# INA381A_Overcurrent_Protection.net
KiCad netlist of a schematic drawn in Altium Designer
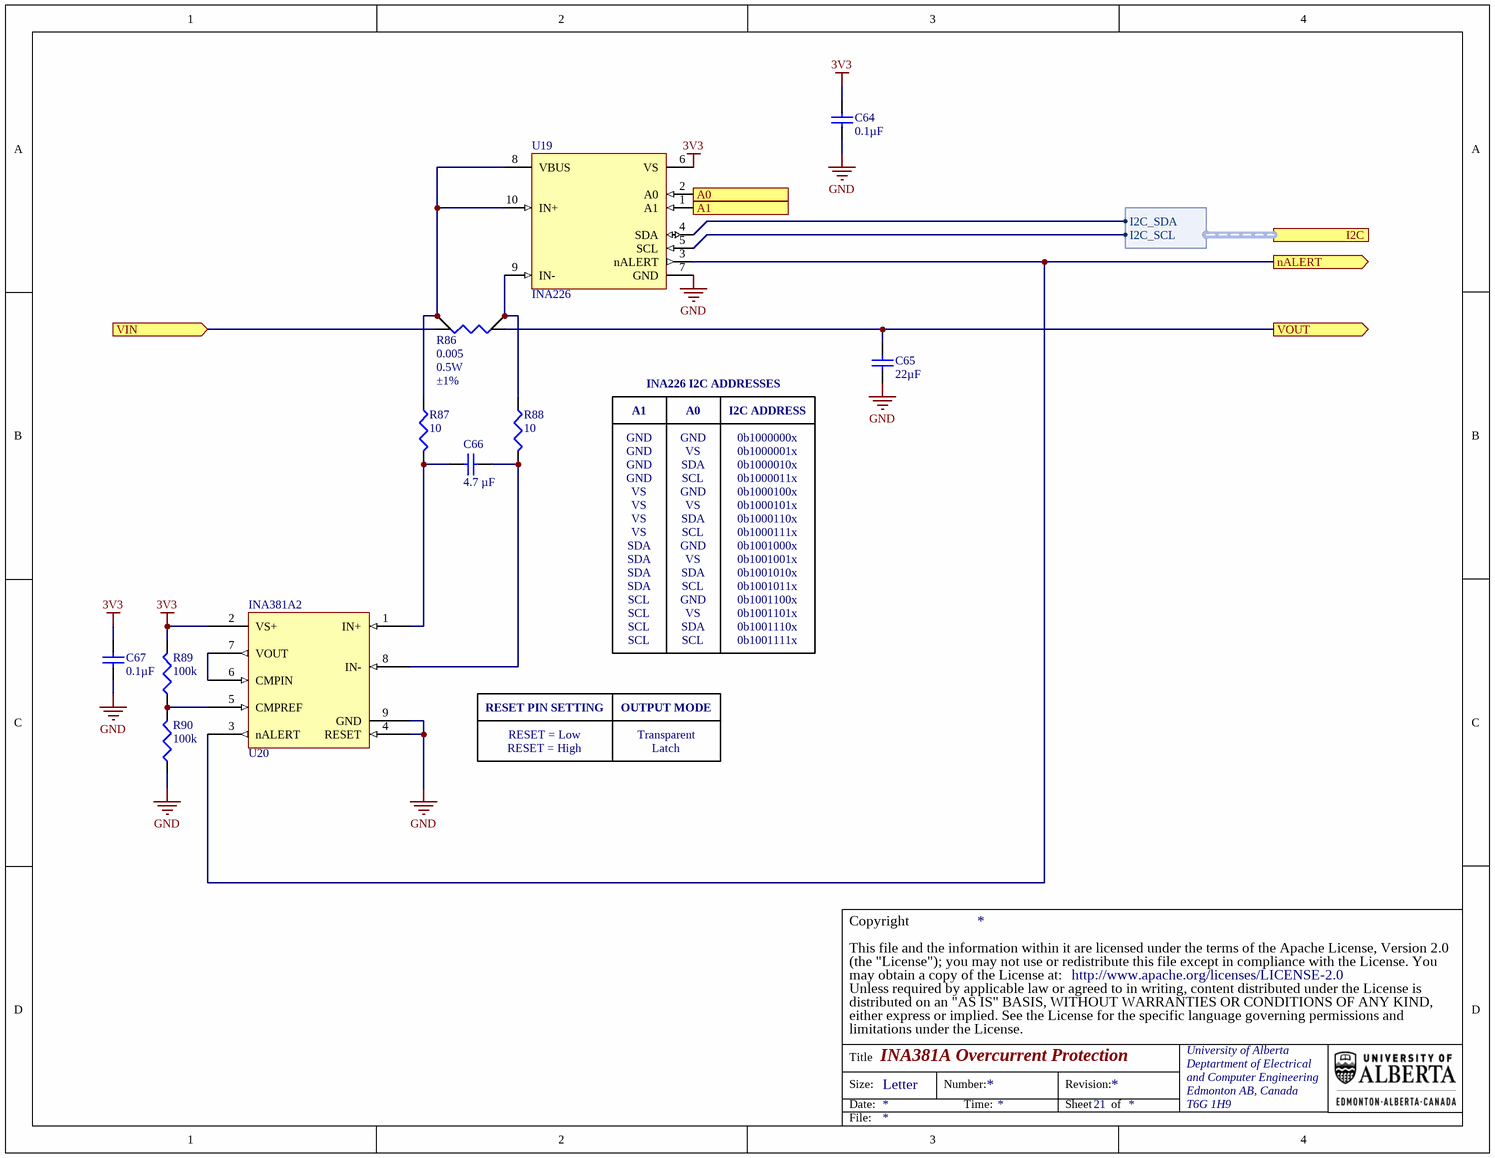
[diagram p0: INA381A Overcurrent Protection.SchDoc]

(export (version "E")
  (design (tool "Eeschema 10.0.6"))
  (components
    (comp (ref "C64")
      (value "0.1µF")
      (footprint "TDK-CGA2B")
      (description "CAP CER 0.1UF 50V X7R 0402")
      (fields
        (field (name "PART NUMBER") "PC-TDK-02259")
        (field (name "MANUFACTURER PART NUMBER") "CGA2B3X7R1H104K050BB")
        (field (name "PUBLISHER") "AlbertaSat")
      )
      (libsource (lib "Database") (part "Cap"))
    )
    (comp (ref "C65")
      (value "22µF")
      (footprint "TY-1206L")
      (description "CAP CER 22UF 16V X7R 1206")
      (fields
        (field (name "PART NUMBER") "PC-TY-00721")
        (field (name "MANUFACTURER PART NUMBER") "EMK316BB7226ML-T")
        (field (name "PUBLISHER") "AlbertaSat")
      )
      (libsource (lib "Database") (part "Cap"))
    )
    (comp (ref "C66")
      (value "4.7 µF")
      (footprint "MUR-GRM188")
      (description "CAP CER 4.7UF 16V X7R 0603")
      (fields
        (field (name "PART NUMBER") "10165")
        (field (name "MANUFACTURER PART NUMBER") "GRM188Z71C475KE21D")
        (field (name "PUBLISHER") "Altium Limited")
      )
      (libsource (lib "Database") (part "Cap"))
    )
    (comp (ref "C67")
      (value "0.1µF")
      (footprint "TDK-CGA2B")
      (description "CAP CER 0.1UF 50V X7R 0402")
      (fields
        (field (name "PART NUMBER") "PC-TDK-02259")
        (field (name "MANUFACTURER PART NUMBER") "CGA2B3X7R1H104K050BB")
        (field (name "PUBLISHER") "AlbertaSat")
      )
      (libsource (lib "Database") (part "Cap"))
    )
    (comp (ref "R86")
      (value "0.005")
      (footprint "BRN-CRF0805")
      (description "RES 0.005 OHM 1% 1/2W 0805")
      (fields
        (field (name "POWER - RATED") "0.5W")
        (field (name "TOLERANCE") "±1%")
        (field (name "PART NUMBER") "PR-BRN-00023")
        (field (name "MANUFACTURER PART NUMBER") "CRF0805-FZ-R005ELF")
        (field (name "PUBLISHER") "AlbertaSat")
      )
      (libsource (lib "Database") (part "Res Sense"))
    )
    (comp (ref "R87")
      (value "10")
      (footprint "PANA-ERA2A")
      (description "RES SMD 10 OHM 0.5% 1/16W 0402")
      (fields
        (field (name "PART NUMBER") "13235")
        (field (name "MANUFACTURER PART NUMBER") "ERA-2AKD100X")
        (field (name "PUBLISHER") "Altium Limited")
      )
      (libsource (lib "Database") (part "Res3"))
    )
    (comp (ref "R88")
      (value "10")
      (footprint "PANA-ERA2A")
      (description "RES SMD 10 OHM 0.5% 1/16W 0402")
      (fields
        (field (name "PART NUMBER") "13235")
        (field (name "MANUFACTURER PART NUMBER") "ERA-2AKD100X")
        (field (name "PUBLISHER") "Altium Limited")
      )
      (libsource (lib "Database") (part "Res3"))
    )
    (comp (ref "R89")
      (value "100k")
      (footprint "PANA-ERJ2R")
      (description "RES SMD 100K OHM 1% 1/10W 0402")
      (fields
        (field (name "PART NUMBER") "18739")
        (field (name "MANUFACTURER PART NUMBER") "ERJ-2RKF1003X")
        (field (name "PUBLISHER") "Altium Limited")
      )
      (libsource (lib "Database") (part "Res3"))
    )
    (comp (ref "R90")
      (value "100k")
      (footprint "PANA-ERJ2R")
      (description "RES SMD 100K OHM 1% 1/10W 0402")
      (fields
        (field (name "PART NUMBER") "18739")
        (field (name "MANUFACTURER PART NUMBER") "ERJ-2RKF1003X")
        (field (name "PUBLISHER") "Altium Limited")
      )
      (libsource (lib "Database") (part "Res3"))
    )
    (comp (ref "U19")
      (value "INA226")
      (footprint "TI-DGS")
      (description "IC MONITOR PWR/CURR BIDIR 10MSOP")
      (fields (field (name "PART NUMBER") "19") (field (name "MANUFACTURER PART NUMBER") "INA226AQDGSRQ1"))
      (libsource (lib "Database") (part "INA226AQ"))
    )
    (comp (ref "U20")
      (value "INA381A2")
      (footprint "TI-DSG0008A")
      (description "CURRENT SENSE AMPLIFIER WITH INT")
      (fields (field (name "PART NUMBER") "110") (field (name "MANUFACTURER PART NUMBER") "INA381A2IDSGT"))
      (libsource (lib "Database") (part "INA381A2DSGT"))
    )
  )
  (nets
    (net (code "2") (name "/A0") (class "Default")
      (node (ref "U19") (pin "2") (pinfunction "A0_2") (pintype "input"))
    )
    (net (code "3") (name "/A1") (class "Default")
      (node (ref "U19") (pin "1") (pinfunction "A1_1") (pintype "input"))
    )
    (net (code "4") (name "/I2C_SCL") (class "Default")
      (node (ref "U19") (pin "5") (pinfunction "SCL_5") (pintype "input"))
    )
    (net (code "5") (name "/I2C_SDA") (class "Default")
      (node (ref "U19") (pin "4") (pinfunction "SDA_4") (pintype "bidirectional"))
    )
    (net (code "6") (name "/VIN") (class "Default")
      (node (ref "R86") (pin "2") (pinfunction "I2_2") (pintype "passive"))
    )
    (net (code "7") (name "/VOUT") (class "Default")
      (node (ref "C65") (pin "2") (pinfunction "2_2") (pintype "passive"))
      (node (ref "R86") (pin "1") (pinfunction "I1_1") (pintype "passive"))
    )
    (net (code "8") (name "/nALERT") (class "Default")
      (node (ref "U19") (pin "3") (pinfunction "nALERT_3") (pintype "output"))
      (node (ref "U20") (pin "3") (pinfunction "nALERT_3") (pintype "output"))
    )
    (net (code "10") (name "3V3") (class "Default")
      (node (ref "C64") (pin "2") (pinfunction "2_2") (pintype "passive"))
      (node (ref "C67") (pin "2") (pinfunction "2_2") (pintype "passive"))
      (node (ref "R89") (pin "2") (pinfunction "2_2") (pintype "passive"))
      (node (ref "U19") (pin "6") (pinfunction "VS_6") (pintype "passive"))
      (node (ref "U20") (pin "2") (pinfunction "VS+_2") (pintype "power_in"))
    )
    (net (code "11") (name "GND") (class "Default")
      (node (ref "C64") (pin "1") (pinfunction "1_1") (pintype "passive"))
      (node (ref "C65") (pin "1") (pinfunction "1_1") (pintype "passive"))
      (node (ref "C67") (pin "1") (pinfunction "1_1") (pintype "passive"))
      (node (ref "R90") (pin "1") (pinfunction "1_1") (pintype "passive"))
      (node (ref "U19") (pin "7") (pinfunction "GND_7") (pintype "power_in"))
      (node (ref "U20") (pin "4") (pinfunction "RESET_4") (pintype "input"))
      (node (ref "U20") (pin "9") (pinfunction "GND_9") (pintype "power_in"))
    )
    (net (code "12") (name "Net-(R86-S1)") (class "Default")
      (node (ref "R86") (pin "4") (pinfunction "S1_4") (pintype "passive"))
      (node (ref "R88") (pin "1") (pinfunction "1_1") (pintype "passive"))
      (node (ref "U19") (pin "9") (pinfunction "IN-_9") (pintype "input"))
    )
    (net (code "13") (name "Net-(R86-S2)") (class "Default")
      (node (ref "R86") (pin "3") (pinfunction "S2_3") (pintype "passive"))
      (node (ref "R87") (pin "1") (pinfunction "1_1") (pintype "passive"))
      (node (ref "U19") (pin "10") (pinfunction "IN+_10") (pintype "input"))
      (node (ref "U19") (pin "8") (pinfunction "VBUS_8") (pintype "power_in"))
    )
    (net (code "14") (name "Net-(U20-CMPIN)") (class "Default")
      (node (ref "U20") (pin "6") (pinfunction "CMPIN_6") (pintype "input"))
      (node (ref "U20") (pin "7") (pinfunction "VOUT_7") (pintype "output"))
    )
    (net (code "15") (name "Net-(U20-CMPREF)") (class "Default")
      (node (ref "R89") (pin "1") (pinfunction "1_1") (pintype "passive"))
      (node (ref "R90") (pin "2") (pinfunction "2_2") (pintype "passive"))
      (node (ref "U20") (pin "5") (pinfunction "CMPREF_5") (pintype "input"))
    )
    (net (code "16") (name "Net-(U20-IN+)") (class "Default")
      (node (ref "C66") (pin "2") (pinfunction "2_2") (pintype "passive"))
      (node (ref "R87") (pin "2") (pinfunction "2_2") (pintype "passive"))
      (node (ref "U20") (pin "1") (pinfunction "IN+_1") (pintype "input"))
    )
    (net (code "17") (name "Net-(U20-IN-)") (class "Default")
      (node (ref "C66") (pin "1") (pinfunction "1_1") (pintype "passive"))
      (node (ref "R88") (pin "2") (pinfunction "2_2") (pintype "passive"))
      (node (ref "U20") (pin "8") (pinfunction "IN-_8") (pintype "input"))
    )
  )
)
